# QSPI.net
KiCad netlist of a schematic drawn in Altium Designer
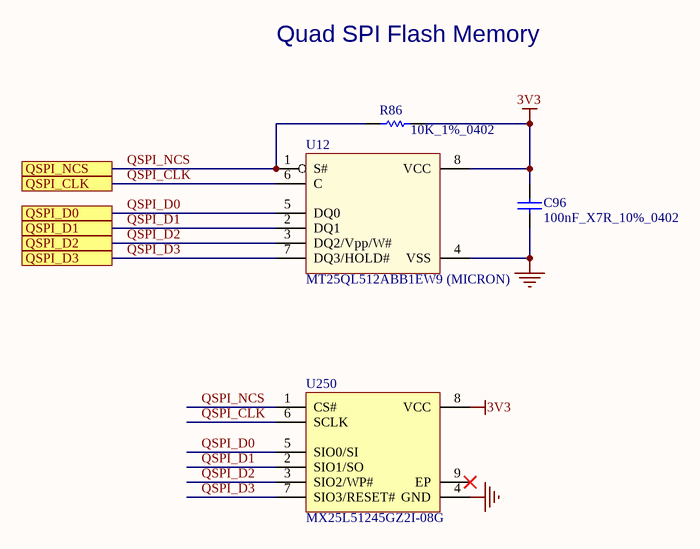
[diagram p0: QSPI.SchDoc]

(export (version "E")
  (design (tool "Eeschema 10.0.6"))
  (components
    (comp (ref "C96")
      (value "100nF_X7R_10%_0402")
      (footprint "0402C")
      (description "Capacitor,100nF,16V,X7R,10%,0402,YAGEO")
      (libsource (lib "MCD_TOOLS") (part "Cap_100nF_X7R_10%_0402"))
    )
    (comp (ref "R86")
      (value "10K_1%_0402")
      (footprint "0402R")
      (description "Resistor,10K,0402,1%,YAGEO")
      (libsource (lib "MCD_TOOLS") (part "Res_10K_1%_0402"))
    )
    (comp (ref "U12")
      (value "MT25QL512ABB1EW9 (MICRON)")
      (footprint "DFN8_1R27_6X8_TP4R8X5R16")
      (description "512Mb, 3V, Multiple I/O Serial Flash Memory, Quad/Dual")
      (libsource (lib "MCD_TOOLS_MISCELLANEOUS") (part "MT25QL512ABB1EW9"))
    )
    (comp (ref "U250")
      (value "MX25L51245GZ2I-08G")
      (footprint "ICC_WSON8-EPAD_8X6_P127")
      (description "3V 512M-BIT CMOS MXSMIO FLASH MEMORY")
      (fields (field (name "INTERNAL_PART_NUMBER") "MCD-01077") (field (name "MANUFACTURER") "MACRONIX"))
      (libsource (lib "MCD_PARTS_database") (part "MX25L51245GZ2I-08G"))
    )
  )
  (nets
    (net (code "1") (name "/QSPI_CLK") (class "Default")
      (node (ref "U12") (pin "6") (pinfunction "C_6") (pintype "passive"))
      (node (ref "U250") (pin "6") (pinfunction "SCLK_6") (pintype "passive"))
    )
    (net (code "2") (name "/QSPI_D0") (class "Default")
      (node (ref "U12") (pin "5") (pinfunction "DQ0_5") (pintype "passive"))
      (node (ref "U250") (pin "5") (pinfunction "SIO0/SI_5") (pintype "passive"))
    )
    (net (code "3") (name "/QSPI_D1") (class "Default")
      (node (ref "U12") (pin "2") (pinfunction "DQ1_2") (pintype "passive"))
      (node (ref "U250") (pin "2") (pinfunction "SIO1/SO_2") (pintype "passive"))
    )
    (net (code "4") (name "/QSPI_D2") (class "Default")
      (node (ref "U12") (pin "3") (pinfunction "DQ2/Vpp/W#_3") (pintype "passive"))
      (node (ref "U250") (pin "3") (pinfunction "SIO2/WP#_3") (pintype "passive"))
    )
    (net (code "5") (name "/QSPI_D3") (class "Default")
      (node (ref "U12") (pin "7") (pinfunction "DQ3/HOLD#_7") (pintype "passive"))
      (node (ref "U250") (pin "7") (pinfunction "SIO3/RESET#_7") (pintype "passive"))
    )
    (net (code "6") (name "/QSPI_NCS") (class "Default")
      (node (ref "R86") (pin "1") (pinfunction "1_1") (pintype "passive"))
      (node (ref "U12") (pin "1") (pinfunction "S#_1") (pintype "passive"))
      (node (ref "U250") (pin "1") (pinfunction "CS#_1") (pintype "passive"))
    )
    (net (code "7") (name "3V3") (class "Default")
      (node (ref "C96") (pin "2") (pinfunction "2_2") (pintype "passive"))
      (node (ref "R86") (pin "2") (pinfunction "2_2") (pintype "passive"))
      (node (ref "U12") (pin "8") (pinfunction "VCC_8") (pintype "passive"))
      (node (ref "U250") (pin "8") (pinfunction "VCC_8") (pintype "passive"))
    )
    (net (code "8") (name "GND") (class "Default")
      (node (ref "C96") (pin "1") (pinfunction "1_1") (pintype "passive"))
      (node (ref "U12") (pin "4") (pinfunction "VSS_4") (pintype "passive"))
      (node (ref "U250") (pin "4") (pinfunction "GND_4") (pintype "passive"))
    )
    (net (code "9") (name "unconnected-(U250-EP-Pad9)") (class "Default")
      (node (ref "U250") (pin "9") (pinfunction "EP_9") (pintype "passive+no_connect"))
    )
  )
)
